# Inputs.net
KiCad netlist of a schematic drawn in Altium Designer
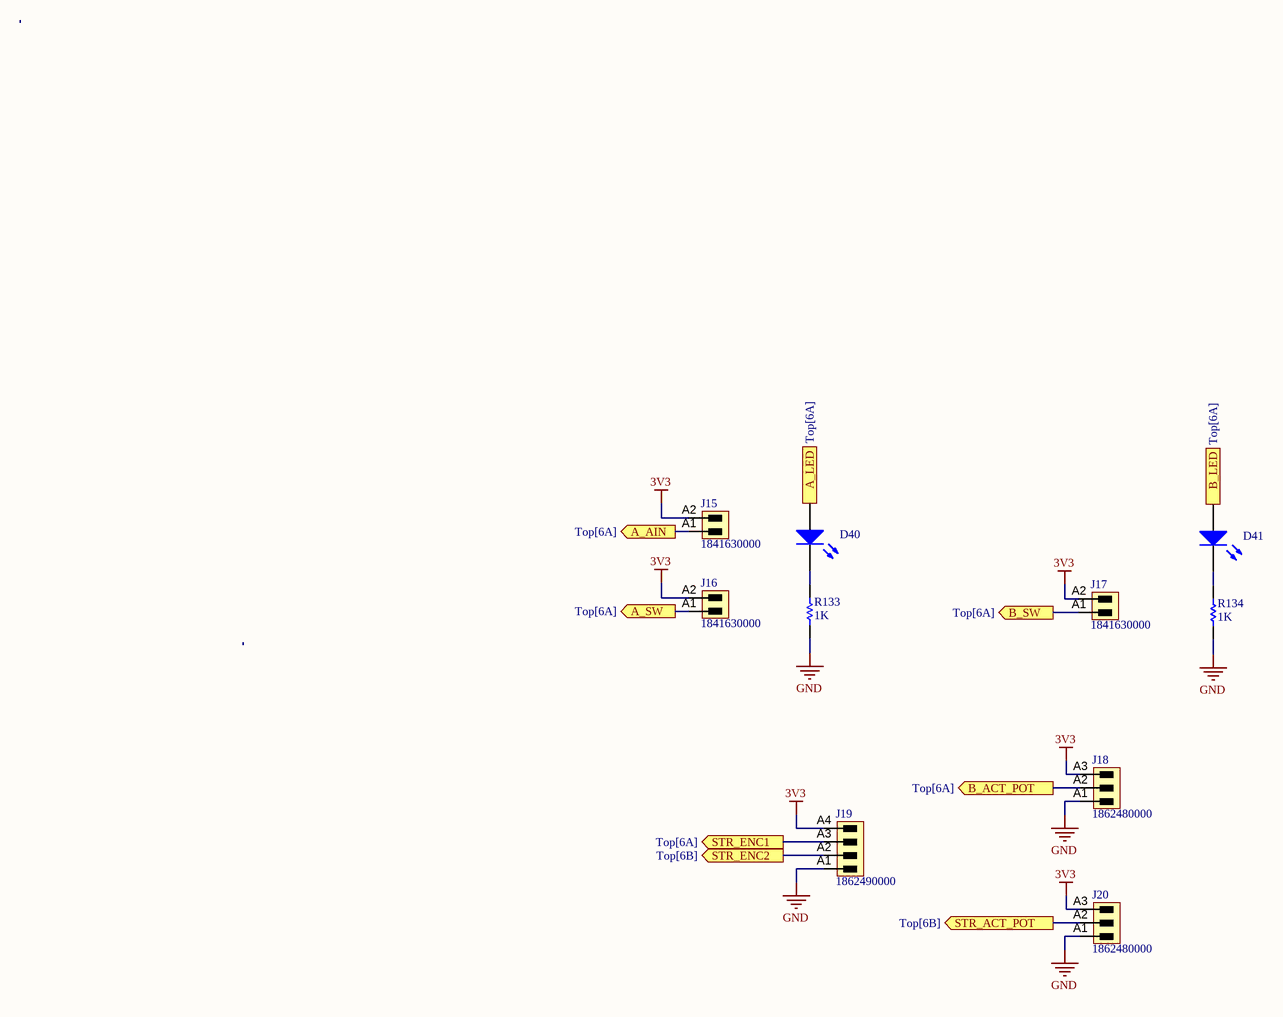
[diagram p0: Inputs.SchDoc]

(export (version "E")
  (design (tool "Eeschema 10.0.6"))
  (components
    (comp (ref "D40")
      (value "Light-Emitting Diode")
      (libsource (lib "Simulation Generic Components") (part "LED"))
    )
    (comp (ref "D41")
      (value "Light-Emitting Diode")
      (libsource (lib "Simulation Generic Components") (part "LED"))
    )
    (comp (ref "J15")
      (value "1841630000")
      (footprint "SL_SMT_3_5_90G_02")
      (description "OMNIMATE Signal - series BL/SL 3.50")
      (fields (field (name "MANUFACTURER") "Weidmueller"))
      (libsource (lib "Altium Content Vault") (part "Header_Male_02_1x02"))
    )
    (comp (ref "J16")
      (value "1841630000")
      (footprint "SL_SMT_3_5_90G_02")
      (description "OMNIMATE Signal - series BL/SL 3.50")
      (fields (field (name "MANUFACTURER") "Weidmueller"))
      (libsource (lib "Altium Content Vault") (part "Header_Male_02_1x02"))
    )
    (comp (ref "J17")
      (value "1841630000")
      (footprint "SL_SMT_3_5_90G_02")
      (description "OMNIMATE Signal - series BL/SL 3.50")
      (fields (field (name "MANUFACTURER") "Weidmueller"))
      (libsource (lib "Altium Content Vault") (part "Header_Male_02_1x02"))
    )
    (comp (ref "J18")
      (value "1862480000")
      (footprint "SC_SMT_3_81_90G_03")
      (description "OMNIMATE Signal - series BC/SC 3.81")
      (fields (field (name "MANUFACTURER") "Weidmueller"))
      (libsource (lib "Altium Content Vault") (part "Header_Male_03_1x03"))
    )
    (comp (ref "J19")
      (value "1862490000")
      (footprint "SC_SMT_3_81_90G_04")
      (description "OMNIMATE Signal - series BC/SC 3.81")
      (fields (field (name "MANUFACTURER") "Weidmueller"))
      (libsource (lib "Altium Content Vault") (part "Header_Male_04_1x04"))
    )
    (comp (ref "J20")
      (value "1862480000")
      (footprint "SC_SMT_3_81_90G_03")
      (description "OMNIMATE Signal - series BC/SC 3.81")
      (fields (field (name "MANUFACTURER") "Weidmueller"))
      (libsource (lib "Altium Content Vault") (part "Header_Male_03_1x03"))
    )
    (comp (ref "R133")
      (value "1K")
      (description "Resistor")
      (libsource (lib "Simulation Generic Components") (part "Resistor"))
    )
    (comp (ref "R134")
      (value "1K")
      (description "Resistor")
      (libsource (lib "Simulation Generic Components") (part "Resistor"))
    )
  )
  (nets
    (net (code "1") (name "/A_AIN") (class "Default")
      (node (ref "J15") (pin "A1") (pinfunction "A1_A1") (pintype "passive"))
    )
    (net (code "2") (name "/A_LED") (class "Default")
      (node (ref "D40") (pin "1") (pinfunction "A_1") (pintype "passive"))
    )
    (net (code "3") (name "/A_SW") (class "Default")
      (node (ref "J16") (pin "A1") (pinfunction "A1_A1") (pintype "passive"))
    )
    (net (code "4") (name "/B_ACT_POT") (class "Default")
      (node (ref "J18") (pin "A2") (pinfunction "A2_A2") (pintype "passive"))
    )
    (net (code "5") (name "/B_LED") (class "Default")
      (node (ref "D41") (pin "1") (pinfunction "A_1") (pintype "passive"))
    )
    (net (code "6") (name "/B_SW") (class "Default")
      (node (ref "J17") (pin "A1") (pinfunction "A1_A1") (pintype "passive"))
    )
    (net (code "7") (name "/STR_ACT_POT") (class "Default")
      (node (ref "J20") (pin "A2") (pinfunction "A2_A2") (pintype "passive"))
    )
    (net (code "8") (name "/STR_ENC1") (class "Default")
      (node (ref "J19") (pin "A3") (pinfunction "A3_A3") (pintype "passive"))
    )
    (net (code "9") (name "/STR_ENC2") (class "Default")
      (node (ref "J19") (pin "A2") (pinfunction "A2_A2") (pintype "passive"))
    )
    (net (code "10") (name "3V3") (class "Default")
      (node (ref "J15") (pin "A2") (pinfunction "A2_A2") (pintype "passive"))
      (node (ref "J16") (pin "A2") (pinfunction "A2_A2") (pintype "passive"))
      (node (ref "J17") (pin "A2") (pinfunction "A2_A2") (pintype "passive"))
      (node (ref "J18") (pin "A3") (pinfunction "A3_A3") (pintype "passive"))
      (node (ref "J19") (pin "A4") (pinfunction "A4_A4") (pintype "passive"))
      (node (ref "J20") (pin "A3") (pinfunction "A3_A3") (pintype "passive"))
    )
    (net (code "11") (name "GND") (class "Default")
      (node (ref "J18") (pin "A1") (pinfunction "A1_A1") (pintype "passive"))
      (node (ref "J19") (pin "A1") (pinfunction "A1_A1") (pintype "passive"))
      (node (ref "J20") (pin "A1") (pinfunction "A1_A1") (pintype "passive"))
      (node (ref "R133") (pin "2") (pinfunction "2_2") (pintype "passive"))
      (node (ref "R134") (pin "2") (pinfunction "2_2") (pintype "passive"))
    )
    (net (code "12") (name "Net-(D40-K)") (class "Default")
      (node (ref "D40") (pin "2") (pinfunction "K_2") (pintype "passive"))
      (node (ref "R133") (pin "1") (pinfunction "1_1") (pintype "passive"))
    )
    (net (code "13") (name "Net-(D41-K)") (class "Default")
      (node (ref "D41") (pin "2") (pinfunction "K_2") (pintype "passive"))
      (node (ref "R134") (pin "1") (pinfunction "1_1") (pintype "passive"))
    )
  )
)
